# 2023_ROBOCON_A_SUB.net
KiCad netlist of a schematic drawn in EAGLE
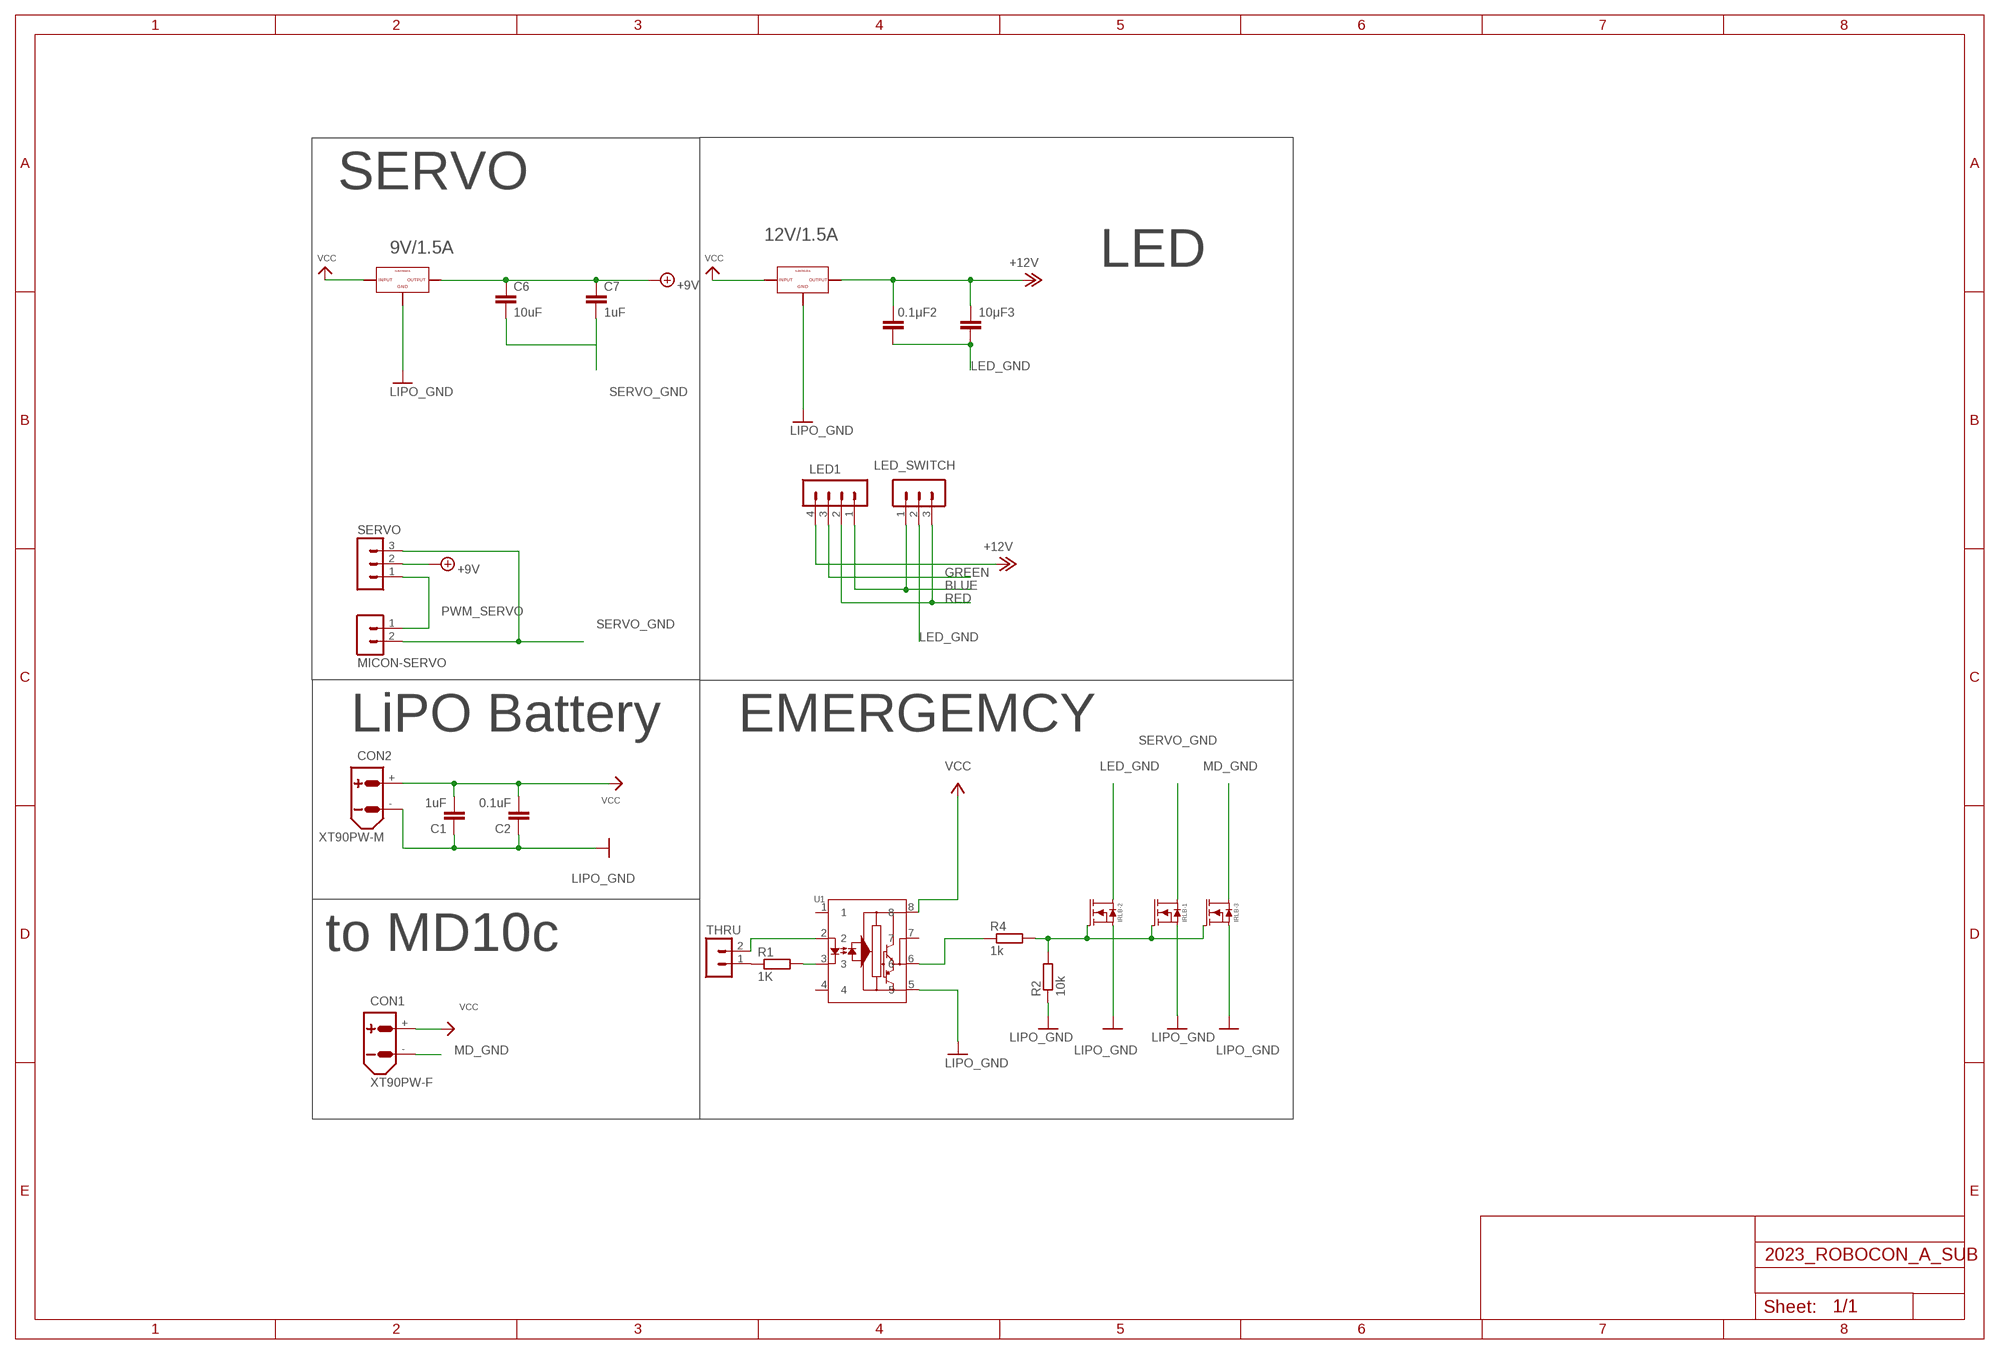
[diagram p0: schematic, sheet 1]

(export (version "E")
  (design (tool "Eeschema 10.0.6"))
  (components
    (comp (ref "0.1μF2")
      (value "C2,5-3")
      (footprint "eagle-import:C2.5-3")
      (libsource (lib "eagle-import") (part "C2,5-3"))
    )
    (comp (ref "10μF3")
      (value "C2,5-3")
      (footprint "eagle-import:C2.5-3")
      (libsource (lib "eagle-import") (part "C2,5-3"))
    )
    (comp (ref "C1")
      (value "1uF")
      (footprint "eagle-import:C2.5-3")
      (libsource (lib "eagle-import") (part "C2,5-3"))
    )
    (comp (ref "C2")
      (value "0.1uF")
      (footprint "eagle-import:C2.5-3")
      (libsource (lib "eagle-import") (part "C2,5-3"))
    )
    (comp (ref "C6")
      (value "10uF")
      (footprint "eagle-import:C2.5-3")
      (libsource (lib "eagle-import") (part "C2,5-3"))
    )
    (comp (ref "C7")
      (value "1uF")
      (footprint "eagle-import:C2.5-3")
      (libsource (lib "eagle-import") (part "C2,5-3"))
    )
    (comp (ref "CON1")
      (value "XT90PW-F")
      (footprint "eagle-import:XT90PW-F")
      (libsource (lib "eagle-import") (part "XT90PW-F"))
    )
    (comp (ref "CON2")
      (value "XT90PW-M")
      (footprint "eagle-import:XT90PW-M")
      (libsource (lib "eagle-import") (part "XT90PW-M"))
    )
    (comp (ref "IRLB-1")
      (value "IRLB3813STAND")
      (footprint "eagle-import:TO-220AB-STAND")
      (libsource (lib "eagle-import") (part "IRLB3813STAND"))
    )
    (comp (ref "IRLB-2")
      (value "IRLB3813STAND")
      (footprint "eagle-import:TO-220AB-STAND")
      (libsource (lib "eagle-import") (part "IRLB3813STAND"))
    )
    (comp (ref "IRLB-3")
      (value "IRLB3813STAND")
      (footprint "eagle-import:TO-220AB-STAND")
      (libsource (lib "eagle-import") (part "IRLB3813STAND"))
    )
    (comp (ref "LED1")
      (value "04-JST")
      (footprint "eagle-import:B4B-XH")
      (libsource (lib "eagle-import") (part "04-JST"))
    )
    (comp (ref "LED_SWITCH")
      (value "03-JST")
      (footprint "eagle-import:B3B-XH")
      (libsource (lib "eagle-import") (part "con-jst-xh_1_03-JST"))
    )
    (comp (ref "MICON-SERVO")
      (value "02-JST")
      (footprint "eagle-import:B2B-XH")
      (libsource (lib "eagle-import") (part "02-JST"))
    )
    (comp (ref "R1")
      (value "1K")
      (footprint "eagle-import:0204_5")
      (libsource (lib "eagle-import") (part "R-EU_0204/5"))
    )
    (comp (ref "R2")
      (value "10k")
      (footprint "eagle-import:0207_7")
      (libsource (lib "eagle-import") (part "R-EU_0207/7"))
    )
    (comp (ref "R4")
      (value "1k")
      (footprint "eagle-import:0207_7")
      (libsource (lib "eagle-import") (part "R-EU_0207/7"))
    )
    (comp (ref "SERVO")
      (value "03-JST")
      (footprint "eagle-import:B3B-XH")
      (libsource (lib "eagle-import") (part "03-JST"))
    )
    (comp (ref "THRU")
      (value "02-JST")
      (footprint "eagle-import:B2B-XH")
      (libsource (lib "eagle-import") (part "con-jst-xh_1_02-JST"))
    )
    (comp (ref "U$4")
      (value "NJM7812FA")
      (footprint "eagle-import:NJM7812FA")
      (libsource (lib "eagle-import") (part "NJM7812FA"))
    )
    (comp (ref "U$7")
      (value "NJM7809FA")
      (footprint "eagle-import:NJM7809FA")
      (libsource (lib "eagle-import") (part "NJM7809FA"))
    )
    (comp (ref "U1")
      (value "TLP-250")
      (footprint "eagle-import:DIP8_TLP250_6P4X9P66_TOS")
      (fields (field (name "COPYRIGHT") "Copyright (C) 2023 Ultra Librarian. All rights reserved."))
      (libsource (lib "eagle-import") (part "TLP-250"))
    )
  )
  (nets
    (net (code "1") (name "+9V") (class "Default")
      (node (ref "C6") (pin "1") (pinfunction "1_1") (pintype "passive"))
      (node (ref "C7") (pin "1") (pinfunction "1_1") (pintype "passive"))
      (node (ref "SERVO") (pin "2") (pinfunction "2_2") (pintype "passive"))
      (node (ref "U$7") (pin "OUTPUT") (pinfunction "OUTPUT_OUTPUT") (pintype "bidirectional"))
    )
    (net (code "2") (name "+12V") (class "Default")
      (node (ref "0.1μF2") (pin "1") (pinfunction "1_1") (pintype "passive"))
      (node (ref "10μF3") (pin "1") (pinfunction "1_1") (pintype "passive"))
      (node (ref "LED1") (pin "4") (pinfunction "4_4") (pintype "passive"))
      (node (ref "U$4") (pin "OUTPUT") (pinfunction "OUTPUT_OUTPUT") (pintype "bidirectional"))
    )
    (net (code "3") (name "/BLUE") (class "Default")
      (node (ref "LED1") (pin "1") (pinfunction "1_1") (pintype "passive"))
      (node (ref "LED_SWITCH") (pin "1") (pinfunction "1_1") (pintype "passive"))
    )
    (net (code "4") (name "/GREEN") (class "Default")
      (node (ref "LED1") (pin "3") (pinfunction "3_3") (pintype "passive"))
    )
    (net (code "5") (name "/LED_GND") (class "Default")
      (node (ref "0.1μF2") (pin "2") (pinfunction "2_2") (pintype "passive"))
      (node (ref "10μF3") (pin "2") (pinfunction "2_2") (pintype "passive"))
      (node (ref "IRLB-2") (pin "D") (pinfunction "D_D") (pintype "passive"))
      (node (ref "LED_SWITCH") (pin "2") (pinfunction "2_2") (pintype "passive"))
    )
    (net (code "6") (name "/MD_GND") (class "Default")
      (node (ref "CON1") (pin "-") (pinfunction "-_-") (pintype "power_in"))
      (node (ref "IRLB-3") (pin "D") (pinfunction "D_D") (pintype "passive"))
    )
    (net (code "7") (name "/PWM_SERVO") (class "Default")
      (node (ref "MICON-SERVO") (pin "1") (pinfunction "1_1") (pintype "passive"))
      (node (ref "SERVO") (pin "1") (pinfunction "1_1") (pintype "passive"))
    )
    (net (code "8") (name "/RED") (class "Default")
      (node (ref "LED1") (pin "2") (pinfunction "2_2") (pintype "passive"))
      (node (ref "LED_SWITCH") (pin "3") (pinfunction "3_3") (pintype "passive"))
    )
    (net (code "9") (name "/SERVO_GND") (class "Default")
      (node (ref "C6") (pin "2") (pinfunction "2_2") (pintype "passive"))
      (node (ref "C7") (pin "2") (pinfunction "2_2") (pintype "passive"))
      (node (ref "IRLB-1") (pin "D") (pinfunction "D_D") (pintype "passive"))
      (node (ref "MICON-SERVO") (pin "2") (pinfunction "2_2") (pintype "passive"))
      (node (ref "SERVO") (pin "3") (pinfunction "3_3") (pintype "passive"))
    )
    (net (code "10") (name "LIPO_GND") (class "Default")
      (node (ref "C1") (pin "1") (pinfunction "1_1") (pintype "passive"))
      (node (ref "C2") (pin "1") (pinfunction "1_1") (pintype "passive"))
      (node (ref "CON2") (pin "-") (pinfunction "-_-") (pintype "power_in"))
      (node (ref "IRLB-1") (pin "S") (pinfunction "S_S") (pintype "passive"))
      (node (ref "IRLB-2") (pin "S") (pinfunction "S_S") (pintype "passive"))
      (node (ref "IRLB-3") (pin "S") (pinfunction "S_S") (pintype "passive"))
      (node (ref "R2") (pin "1") (pinfunction "1_1") (pintype "passive"))
      (node (ref "U$4") (pin "GND") (pinfunction "GND_GND") (pintype "bidirectional"))
      (node (ref "U$7") (pin "GND") (pinfunction "GND_GND") (pintype "bidirectional"))
      (node (ref "U1") (pin "5") (pinfunction "5_5") (pintype "passive"))
    )
    (net (code "11") (name "Net-(IRLB-1-PadG)") (class "Default")
      (node (ref "IRLB-1") (pin "G") (pinfunction "G_G") (pintype "passive"))
      (node (ref "IRLB-2") (pin "G") (pinfunction "G_G") (pintype "passive"))
      (node (ref "IRLB-3") (pin "G") (pinfunction "G_G") (pintype "passive"))
      (node (ref "R2") (pin "2") (pinfunction "2_2") (pintype "passive"))
      (node (ref "R4") (pin "2") (pinfunction "2_2") (pintype "passive"))
    )
    (net (code "12") (name "Net-(R1-Pad1)") (class "Default")
      (node (ref "R1") (pin "1") (pinfunction "1_1") (pintype "passive"))
      (node (ref "THRU") (pin "1") (pinfunction "1_1") (pintype "passive"))
    )
    (net (code "13") (name "Net-(R1-Pad2)") (class "Default")
      (node (ref "R1") (pin "2") (pinfunction "2_2") (pintype "passive"))
      (node (ref "U1") (pin "3") (pinfunction "3_3") (pintype "passive"))
    )
    (net (code "14") (name "Net-(R4-Pad1)") (class "Default")
      (node (ref "R4") (pin "1") (pinfunction "1_1") (pintype "passive"))
      (node (ref "U1") (pin "6") (pinfunction "6_6") (pintype "passive"))
    )
    (net (code "15") (name "Net-(THRU-Pad2)") (class "Default")
      (node (ref "THRU") (pin "2") (pinfunction "2_2") (pintype "passive"))
      (node (ref "U1") (pin "2") (pinfunction "2_2") (pintype "passive"))
    )
    (net (code "16") (name "VCC") (class "Default")
      (node (ref "C1") (pin "2") (pinfunction "2_2") (pintype "passive"))
      (node (ref "C2") (pin "2") (pinfunction "2_2") (pintype "passive"))
      (node (ref "CON1") (pin "+") (pinfunction "+_+") (pintype "power_in"))
      (node (ref "CON2") (pin "+") (pinfunction "+_+") (pintype "power_in"))
      (node (ref "U$4") (pin "INPUT") (pinfunction "INPUT_INPUT") (pintype "bidirectional"))
      (node (ref "U$7") (pin "INPUT") (pinfunction "INPUT_INPUT") (pintype "bidirectional"))
      (node (ref "U1") (pin "8") (pinfunction "8_8") (pintype "power_in"))
    )
    (net (code "17") (name "unconnected-(U1-Pad1)") (class "Default")
      (node (ref "U1") (pin "1") (pinfunction "1_1") (pintype "no_connect"))
    )
    (net (code "18") (name "unconnected-(U1-Pad4)") (class "Default")
      (node (ref "U1") (pin "4") (pinfunction "4_4") (pintype "no_connect"))
    )
    (net (code "19") (name "unconnected-(U1-Pad7)") (class "Default")
      (node (ref "U1") (pin "7") (pinfunction "7_7") (pintype "passive"))
    )
  )
)
